# Remote.net
KiCad netlist of a schematic drawn in Altium Designer
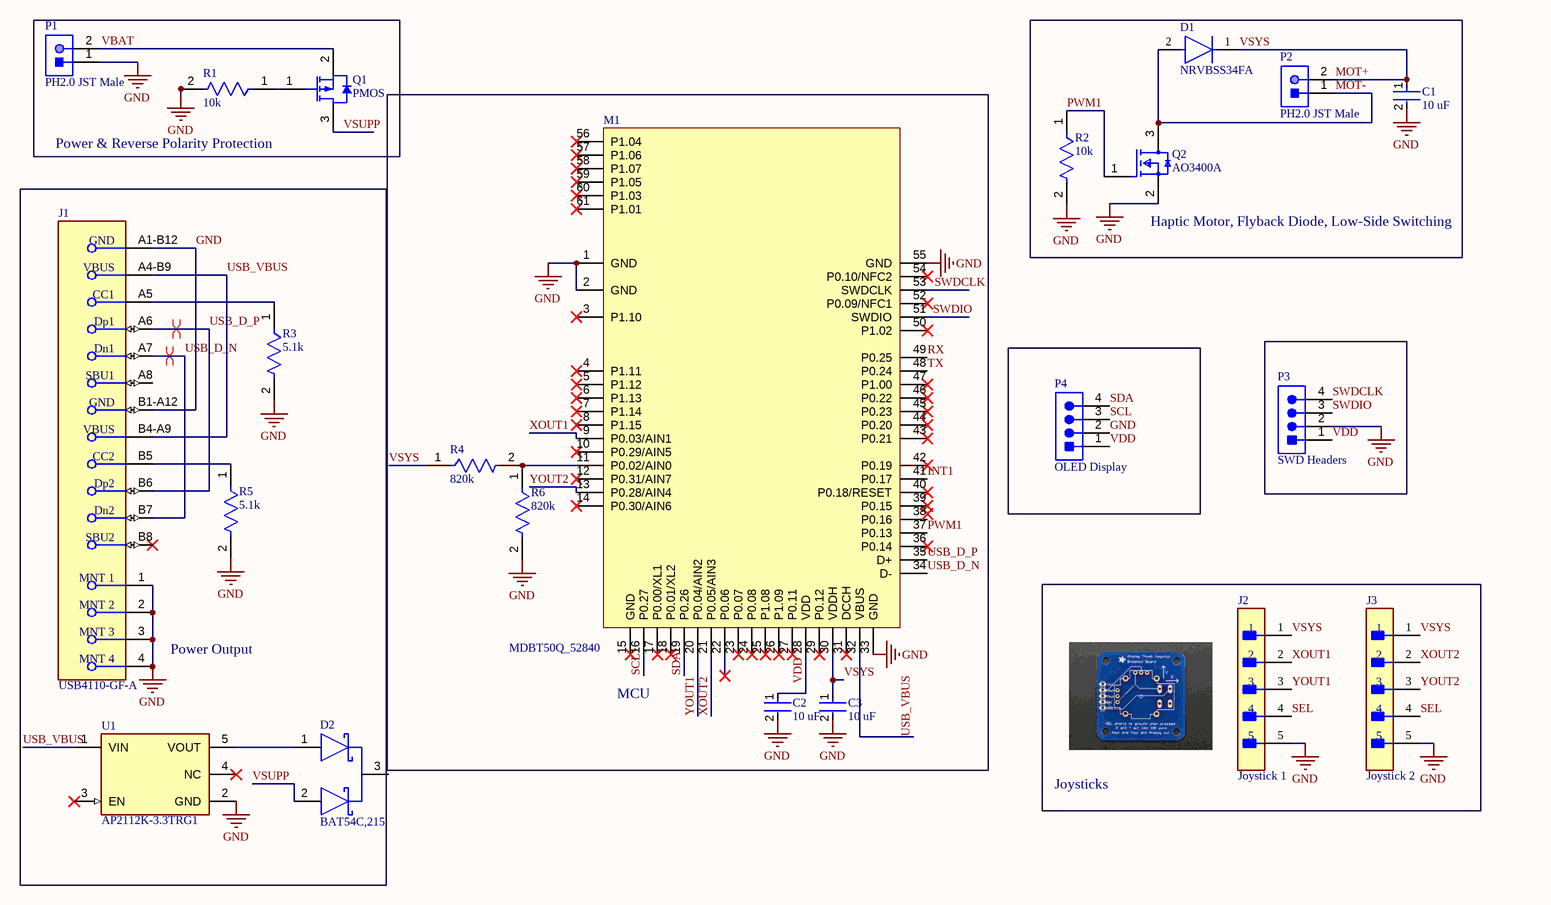
[diagram p0: Remote.SchDoc]

(export (version "E")
  (design (tool "Eeschema 10.0.6"))
  (components
    (comp (ref "C1")
      (value "10 uF")
      (footprint "FP-1210-L_3_3_0_4-W_2_5_0-IPC_A")
      (description "CAP CER 10UF 10V X7R 1210, 1210ZC106KAT2A")
      (fields (field (name "VOLTAGE") "10V") (field (name "TOLERANCE") "10%"))
      (libsource (lib "Altium Content Vault") (part "b4654b650e69147ec39a6b967a45e02"))
    )
    (comp (ref "C2")
      (value "10 uF")
      (footprint "FP-1210-L_3_3_0_4-W_2_5_0-IPC_A")
      (description "CAP CER 10UF 10V X7R 1210, 1210ZC106KAT2A")
      (fields (field (name "VOLTAGE") "10V") (field (name "TOLERANCE") "10%"))
      (libsource (lib "Altium Content Vault") (part "b4654b650e69147ec39a6b967a45e02"))
    )
    (comp (ref "C3")
      (value "10 uF")
      (footprint "FP-1210-L_3_3_0_4-W_2_5_0-IPC_A")
      (description "CAP CER 10UF 10V X7R 1210, 1210ZC106KAT2A")
      (fields (field (name "VOLTAGE") "10V") (field (name "TOLERANCE") "10%"))
      (libsource (lib "Altium Content Vault") (part "b4654b650e69147ec39a6b967a45e02"))
    )
    (comp (ref "D1")
      (value "NRVBSS34FA")
      (footprint "FP-425AB-MFG")
      (description "NRVBSS34FA Schottky Barrier Rectifier Diode 40V 3A 2-Pin SOD−123FL T/R")
      (libsource (lib "Altium Content Vault") (part "d7152d700b627762746794eb795d46e"))
    )
    (comp (ref "D2")
      (value "BAT54C,215")
      (footprint "FP-SOT23-MFG")
      (description "DIODE ARRAY SCHOTTKY 30V SOT23")
      (fields
        (field (name "MANUFACTURER") "Nexperia")
        (field (name "OCTOPART") "https://octopart.com/bat54c%2C215-nexperia-78738945")
      )
      (libsource (lib "Altium Content Vault") (part "933c91619b22c421400e34e7415f7b4"))
    )
    (comp (ref "J1")
      (value "USB4110-GF-A")
      (footprint "FP-USB4110-GF-A-MFG")
      (description "CONN USB 2.0 TYPE-C R/A SMT")
      (fields
        (field (name "OCTOPART") "https://octopart.com/usb4110-gf-a-gct-103941985")
        (field (name "MANUFACTURER") "GCT")
      )
      (libsource (lib "Altium Content Vault") (part "e23f2b38bb3c3f98e683ebab9ede730"))
    )
    (comp (ref "J2")
      (value "Joystick 1")
      (footprint "FP-22-28-4050-MFG")
      (libsource (lib "Altium Content Vault") (part "bf93c07fd2649a848d0ec8585582aab"))
    )
    (comp (ref "J3")
      (value "Joystick 2")
      (footprint "FP-22-28-4050-MFG")
      (libsource (lib "Altium Content Vault") (part "bf93c07fd2649a848d0ec8585582aab"))
    )
    (comp (ref "M1")
      (value "MDBT50Q_52840")
      (footprint "MDBT50Q")
      (description "MDBT50Q(52840)")
      (libsource (lib "MDBT50Q_52840_230606") (part "MDBT50Q_52840"))
    )
    (comp (ref "P1")
      (value "PH2.0 JST Male")
      (footprint "JST-S2B-PH-K-S_V")
      (fields (field (name "MANUFACTURER") "Japan Solderless Terminals"))
      (libsource (lib "Altium 365 Cloud") (part "CN-1P-M-R2"))
    )
    (comp (ref "P2")
      (value "PH2.0 JST Male")
      (footprint "JST-S2B-PH-K-S_V")
      (fields (field (name "MANUFACTURER") "Japan Solderless Terminals"))
      (libsource (lib "Altium 365 Cloud") (part "CN-1P-M-R2"))
    )
    (comp (ref "P3")
      (value "SWD Headers")
      (footprint "SLIN-GRPB041VWVN-RC_V")
      (fields (field (name "MANUFACTURER") "Sullins"))
      (libsource (lib "Altium Content Vault") (part "CN-1P-M-R4"))
    )
    (comp (ref "P4")
      (value "OLED Display")
      (footprint "SLIN-GRPB041VWVN-RC_V")
      (fields (field (name "MANUFACTURER") "Sullins"))
      (libsource (lib "Altium Content Vault") (part "CN-1P-M-R4"))
    )
    (comp (ref "Q1")
      (value "PMOS")
      (footprint "AO-SOT-23-3L_V")
      (description "P-Channel MOSFET, 30 V, 4 A, -55 to 150 degC, 3-Pin SOT-23-3L, RoHS, Tape and Reel, AO3401A")
      (fields (field (name "MANUFACTURER") "Alpha and Omega"))
      (libsource (lib "Altium Content Vault") (part "PEMOS-GSD-3"))
    )
    (comp (ref "Q2")
      (value "AO3400A")
      (footprint "FP-SOT23-MFG")
      (description "MOSFET N-CH 30V 5.7A SOT23")
      (libsource (lib "Altium Content Vault") (part "0a9ea7c96deaaede766a5b531c28de0"))
    )
    (comp (ref "R1")
      (value "10k")
      (footprint "FP-CRGCQ1210-IPC_C")
      (description "CRGCQ1210 10KΩ 0.5W ±100ppm/°C 5% 200V")
      (fields (field (name "TOLERANCE") "0.05") (field (name "MANUFACTURER PART NUMBER") "CRGCQ1210J10K"))
      (libsource (lib "Altium Content Vault") (part "1029c3af85768c4190bb7ad29bc67b5"))
    )
    (comp (ref "R2")
      (value "10k")
      (footprint "FP-CRGCQ1210-IPC_C")
      (description "CRGCQ1210 10KΩ 0.5W ±100ppm/°C 5% 200V")
      (fields (field (name "TOLERANCE") "0.05") (field (name "MANUFACTURER PART NUMBER") "CRGCQ1210J10K"))
      (libsource (lib "Altium Content Vault") (part "1029c3af85768c4190bb7ad29bc67b5"))
    )
    (comp (ref "R3")
      (value "5.1k")
      (footprint "FP-ESR10-IPC_C")
      (description "5.1kΩ ±5% 0.4W 0805 Anti-Surge Chip Resistor AEC-Q200")
      (fields (field (name "TOLERANCE") "5%"))
      (libsource (lib "Altium Content Vault") (part "1029c3af85768c4190bb7ad29bc67b5"))
    )
    (comp (ref "R4")
      (value "820k")
      (footprint "FP-AC1206-MFG")
      (description "RES SMD 820K OHM 1% 1/4W 1206, AC1206FR-07820KL")
      (fields
        (field (name "TOLERANCE") "0.01")
        (field (name "OCTOPART") "https://octopart.com/ac1206fr-07820kl-yageo-71368214")
      )
      (libsource (lib "Altium Content Vault") (part "1029c3af85768c4190bb7ad29bc67b5"))
    )
    (comp (ref "R5")
      (value "5.1k")
      (footprint "FP-ESR10-IPC_C")
      (description "5.1kΩ ±5% 0.4W 0805 Anti-Surge Chip Resistor AEC-Q200")
      (fields (field (name "TOLERANCE") "5%"))
      (libsource (lib "Altium Content Vault") (part "1029c3af85768c4190bb7ad29bc67b5"))
    )
    (comp (ref "R6")
      (value "820k")
      (footprint "FP-AC1206-MFG")
      (description "RES SMD 820K OHM 1% 1/4W 1206, AC1206FR-07820KL")
      (fields
        (field (name "TOLERANCE") "0.01")
        (field (name "OCTOPART") "https://octopart.com/ac1206fr-07820kl-yageo-71368214")
      )
      (libsource (lib "Altium Content Vault") (part "1029c3af85768c4190bb7ad29bc67b5"))
    )
    (comp (ref "U1")
      (value "AP2112K-3.3TRG1")
      (footprint "FP-SOT25-IPC_A")
      (description "IC REG LINEAR 3.3V 600MA SOT25")
      (libsource (lib "Altium Content Vault") (part "c8ab751aee5229183125ab046a11caa"))
    )
  )
  (nets
    (net (code "1") (name "/INT1") (class "Default")
      (node (ref "M1") (pin "41") (pinfunction "P0.17_41") (pintype "passive"))
    )
    (net (code "2") (name "/MOT+") (class "Default")
      (node (ref "C1") (pin "1") (pinfunction "1_1") (pintype "passive"))
      (node (ref "C3") (pin "1") (pinfunction "1_1") (pintype "passive"))
      (node (ref "D1") (pin "1") (pinfunction "C_1") (pintype "passive"))
      (node (ref "J2") (pin "1") (pinfunction "1_1") (pintype "passive"))
      (node (ref "J3") (pin "1") (pinfunction "1_1") (pintype "passive"))
      (node (ref "M1") (pin "30") (pinfunction "VDDH_30") (pintype "passive"))
      (node (ref "P2") (pin "2") (pinfunction "2_2") (pintype "passive"))
      (node (ref "R4") (pin "1") (pinfunction "1_1") (pintype "passive"))
    )
    (net (code "3") (name "/MOT-") (class "Default")
      (node (ref "D1") (pin "2") (pinfunction "A_2") (pintype "passive"))
      (node (ref "P2") (pin "1") (pinfunction "1_1") (pintype "passive"))
      (node (ref "Q2") (pin "3") (pinfunction "D_3") (pintype "passive"))
    )
    (net (code "4") (name "/PWM1") (class "Default")
      (node (ref "M1") (pin "37") (pinfunction "P0.13_37") (pintype "passive"))
      (node (ref "Q2") (pin "1") (pinfunction "G_1") (pintype "passive"))
      (node (ref "R2") (pin "1") (pinfunction "1_1") (pintype "passive"))
    )
    (net (code "5") (name "/RX") (class "Default")
      (node (ref "M1") (pin "49") (pinfunction "P0.25_49") (pintype "passive"))
    )
    (net (code "6") (name "/SCL") (class "Default")
      (node (ref "M1") (pin "16") (pinfunction "P0.27_16") (pintype "passive"))
      (node (ref "P4") (pin "3") (pinfunction "3_3") (pintype "passive"))
    )
    (net (code "7") (name "/SDA") (class "Default")
      (node (ref "M1") (pin "19") (pinfunction "P0.26_19") (pintype "passive"))
      (node (ref "P4") (pin "4") (pinfunction "4_4") (pintype "passive"))
    )
    (net (code "8") (name "/SEL") (class "Default")
      (node (ref "J2") (pin "4") (pinfunction "4_4") (pintype "passive"))
      (node (ref "J3") (pin "4") (pinfunction "4_4") (pintype "passive"))
    )
    (net (code "9") (name "/SWDCLK") (class "Default")
      (node (ref "M1") (pin "53") (pinfunction "SWDCLK_53") (pintype "passive"))
      (node (ref "P3") (pin "4") (pinfunction "4_4") (pintype "passive"))
    )
    (net (code "10") (name "/SWDIO") (class "Default")
      (node (ref "M1") (pin "51") (pinfunction "SWDIO_51") (pintype "passive"))
      (node (ref "P3") (pin "3") (pinfunction "3_3") (pintype "passive"))
    )
    (net (code "11") (name "/TX") (class "Default")
      (node (ref "M1") (pin "48") (pinfunction "P0.24_48") (pintype "passive"))
    )
    (net (code "12") (name "/USB_D_N") (class "Default")
      (node (ref "J1") (pin "A7") (pinfunction "Dn1_A7") (pintype "bidirectional"))
      (node (ref "J1") (pin "B7") (pinfunction "Dn2_B7") (pintype "bidirectional"))
      (node (ref "M1") (pin "34") (pinfunction "D-_34") (pintype "passive"))
    )
    (net (code "13") (name "/USB_D_P") (class "Default")
      (node (ref "J1") (pin "A6") (pinfunction "Dp1_A6") (pintype "bidirectional"))
      (node (ref "J1") (pin "B6") (pinfunction "Dp2_B6") (pintype "bidirectional"))
      (node (ref "M1") (pin "35") (pinfunction "D+_35") (pintype "passive"))
    )
    (net (code "14") (name "/USB_VBUS") (class "Default")
      (node (ref "J1") (pin "A4-B9") (pinfunction "VBUS_A4-B9") (pintype "power_in"))
      (node (ref "J1") (pin "B4-A9") (pinfunction "VBUS_B4-A9") (pintype "power_in"))
      (node (ref "M1") (pin "32") (pinfunction "VBUS_32") (pintype "passive"))
      (node (ref "U1") (pin "1") (pinfunction "VIN_1") (pintype "power_in"))
    )
    (net (code "15") (name "/VBAT") (class "Default")
      (node (ref "P1") (pin "2") (pinfunction "2_2") (pintype "passive"))
      (node (ref "Q1") (pin "2") (pinfunction "SOURCE_2") (pintype "passive"))
    )
    (net (code "16") (name "/VDD") (class "Default")
      (node (ref "C2") (pin "1") (pinfunction "1_1") (pintype "passive"))
      (node (ref "M1") (pin "28") (pinfunction "VDD_28") (pintype "passive"))
      (node (ref "P3") (pin "1") (pinfunction "1_1") (pintype "passive"))
      (node (ref "P4") (pin "1") (pinfunction "1_1") (pintype "passive"))
    )
    (net (code "17") (name "/VSUPP") (class "Default")
      (node (ref "D2") (pin "2") (pinfunction "2_ANODE_2") (pintype "passive"))
      (node (ref "Q1") (pin "3") (pinfunction "DRAIN_3") (pintype "passive"))
    )
    (net (code "18") (name "/XOUT1") (class "Default")
      (node (ref "J2") (pin "2") (pinfunction "2_2") (pintype "passive"))
      (node (ref "M1") (pin "9") (pinfunction "P0.03/AIN1_9") (pintype "passive"))
    )
    (net (code "19") (name "/XOUT2") (class "Default")
      (node (ref "J3") (pin "2") (pinfunction "2_2") (pintype "passive"))
      (node (ref "M1") (pin "21") (pinfunction "P0.05/AIN3_21") (pintype "passive"))
    )
    (net (code "20") (name "/YOUT1") (class "Default")
      (node (ref "J2") (pin "3") (pinfunction "3_3") (pintype "passive"))
      (node (ref "M1") (pin "20") (pinfunction "P0.04/AIN2_20") (pintype "passive"))
    )
    (net (code "21") (name "/YOUT2") (class "Default")
      (node (ref "J3") (pin "3") (pinfunction "3_3") (pintype "passive"))
      (node (ref "M1") (pin "13") (pinfunction "P0.28/AIN4_13") (pintype "passive"))
    )
    (net (code "22") (name "GND") (class "Default")
      (node (ref "C1") (pin "2") (pinfunction "2_2") (pintype "passive"))
      (node (ref "C2") (pin "2") (pinfunction "2_2") (pintype "passive"))
      (node (ref "C3") (pin "2") (pinfunction "2_2") (pintype "passive"))
      (node (ref "J1") (pin "1") (pinfunction "MNT_1_1") (pintype "passive"))
      (node (ref "J1") (pin "2") (pinfunction "MNT_2_2") (pintype "passive"))
      (node (ref "J1") (pin "3") (pinfunction "MNT_3_3") (pintype "passive"))
      (node (ref "J1") (pin "4") (pinfunction "MNT_4_4") (pintype "passive"))
      (node (ref "J1") (pin "A1-B12") (pinfunction "GND_A1-B12") (pintype "passive"))
      (node (ref "J1") (pin "B1-A12") (pinfunction "GND_B1-A12") (pintype "bidirectional"))
      (node (ref "J2") (pin "5") (pinfunction "5_5") (pintype "passive"))
      (node (ref "J3") (pin "5") (pinfunction "5_5") (pintype "passive"))
      (node (ref "M1") (pin "1") (pinfunction "GND_1") (pintype "passive"))
      (node (ref "M1") (pin "2") (pinfunction "GND_2") (pintype "passive"))
      (node (ref "M1") (pin "33") (pinfunction "GND_33") (pintype "passive"))
      (node (ref "M1") (pin "55") (pinfunction "GND_55") (pintype "passive"))
      (node (ref "P1") (pin "1") (pinfunction "1_1") (pintype "passive"))
      (node (ref "P3") (pin "2") (pinfunction "2_2") (pintype "passive"))
      (node (ref "P4") (pin "2") (pinfunction "2_2") (pintype "passive"))
      (node (ref "Q2") (pin "2") (pinfunction "S_2") (pintype "passive"))
      (node (ref "R1") (pin "2") (pinfunction "2_2") (pintype "passive"))
      (node (ref "R2") (pin "2") (pinfunction "2_2") (pintype "passive"))
      (node (ref "R3") (pin "2") (pinfunction "2_2") (pintype "passive"))
      (node (ref "R5") (pin "2") (pinfunction "2_2") (pintype "passive"))
      (node (ref "R6") (pin "2") (pinfunction "2_2") (pintype "passive"))
      (node (ref "U1") (pin "2") (pinfunction "GND_2") (pintype "power_in"))
    )
    (net (code "23") (name "Net-(D2-1_ANODE)") (class "Default")
      (node (ref "D2") (pin "1") (pinfunction "1_ANODE_1") (pintype "passive"))
      (node (ref "U1") (pin "5") (pinfunction "VOUT_5") (pintype "power_in"))
    )
    (net (code "24") (name "Net-(J1-CC1)") (class "Default")
      (node (ref "J1") (pin "A5") (pinfunction "CC1_A5") (pintype "power_in"))
      (node (ref "R3") (pin "1") (pinfunction "1_1") (pintype "passive"))
    )
    (net (code "25") (name "Net-(J1-CC2)") (class "Default")
      (node (ref "J1") (pin "B5") (pinfunction "CC2_B5") (pintype "power_in"))
      (node (ref "R5") (pin "1") (pinfunction "1_1") (pintype "passive"))
    )
    (net (code "26") (name "Net-(M1-P0.02{slash}AIN0)") (class "Default")
      (node (ref "M1") (pin "11") (pinfunction "P0.02/AIN0_11") (pintype "passive"))
      (node (ref "R4") (pin "2") (pinfunction "2_2") (pintype "passive"))
      (node (ref "R6") (pin "1") (pinfunction "1_1") (pintype "passive"))
    )
    (net (code "27") (name "Net-(Q1-GATE)") (class "Default")
      (node (ref "Q1") (pin "1") (pinfunction "GATE_1") (pintype "passive"))
      (node (ref "R1") (pin "1") (pinfunction "1_1") (pintype "passive"))
    )
    (net (code "28") (name "unconnected-(D2-COMMON_CATHODE-Pad3)") (class "Default")
      (node (ref "D2") (pin "3") (pinfunction "COMMON_CATHODE_3") (pintype "passive"))
    )
    (net (code "29") (name "unconnected-(J1-SBU1-PadA8)") (class "Default")
      (node (ref "J1") (pin "A8") (pinfunction "SBU1_A8") (pintype "bidirectional"))
    )
    (net (code "30") (name "unconnected-(J1-SBU2-PadB8)") (class "Default")
      (node (ref "J1") (pin "B8") (pinfunction "SBU2_B8") (pintype "bidirectional+no_connect"))
    )
    (net (code "31") (name "unconnected-(M1-DCCH-Pad31)") (class "Default")
      (node (ref "M1") (pin "31") (pinfunction "DCCH_31") (pintype "passive+no_connect"))
    )
    (net (code "32") (name "unconnected-(M1-GND-Pad15)") (class "Default")
      (node (ref "M1") (pin "15") (pinfunction "GND_15") (pintype "passive+no_connect"))
    )
    (net (code "33") (name "unconnected-(M1-P0.00{slash}XL1-Pad17)") (class "Default")
      (node (ref "M1") (pin "17") (pinfunction "P0.00/XL1_17") (pintype "passive+no_connect"))
    )
    (net (code "34") (name "unconnected-(M1-P0.01{slash}XL2-Pad18)") (class "Default")
      (node (ref "M1") (pin "18") (pinfunction "P0.01/XL2_18") (pintype "passive+no_connect"))
    )
    (net (code "35") (name "unconnected-(M1-P0.06-Pad22)") (class "Default")
      (node (ref "M1") (pin "22") (pinfunction "P0.06_22") (pintype "passive+no_connect"))
    )
    (net (code "36") (name "unconnected-(M1-P0.07-Pad23)") (class "Default")
      (node (ref "M1") (pin "23") (pinfunction "P0.07_23") (pintype "passive+no_connect"))
    )
    (net (code "37") (name "unconnected-(M1-P0.08-Pad24)") (class "Default")
      (node (ref "M1") (pin "24") (pinfunction "P0.08_24") (pintype "passive+no_connect"))
    )
    (net (code "38") (name "unconnected-(M1-P0.09{slash}NFC1-Pad52)") (class "Default")
      (node (ref "M1") (pin "52") (pinfunction "P0.09/NFC1_52") (pintype "passive+no_connect"))
    )
    (net (code "39") (name "unconnected-(M1-P0.10{slash}NFC2-Pad54)") (class "Default")
      (node (ref "M1") (pin "54") (pinfunction "P0.10/NFC2_54") (pintype "passive+no_connect"))
    )
    (net (code "40") (name "unconnected-(M1-P0.11-Pad27)") (class "Default")
      (node (ref "M1") (pin "27") (pinfunction "P0.11_27") (pintype "passive+no_connect"))
    )
    (net (code "41") (name "unconnected-(M1-P0.12-Pad29)") (class "Default")
      (node (ref "M1") (pin "29") (pinfunction "P0.12_29") (pintype "passive+no_connect"))
    )
    (net (code "42") (name "unconnected-(M1-P0.14-Pad36)") (class "Default")
      (node (ref "M1") (pin "36") (pinfunction "P0.14_36") (pintype "passive+no_connect"))
    )
    (net (code "43") (name "unconnected-(M1-P0.15-Pad39)") (class "Default")
      (node (ref "M1") (pin "39") (pinfunction "P0.15_39") (pintype "passive+no_connect"))
    )
    (net (code "44") (name "unconnected-(M1-P0.16-Pad38)") (class "Default")
      (node (ref "M1") (pin "38") (pinfunction "P0.16_38") (pintype "passive"))
    )
    (net (code "45") (name "unconnected-(M1-P0.18{slash}RESET-Pad40)") (class "Default")
      (node (ref "M1") (pin "40") (pinfunction "P0.18/RESET_40") (pintype "passive+no_connect"))
    )
    (net (code "46") (name "unconnected-(M1-P0.19-Pad42)") (class "Default")
      (node (ref "M1") (pin "42") (pinfunction "P0.19_42") (pintype "passive+no_connect"))
    )
    (net (code "47") (name "unconnected-(M1-P0.20-Pad44)") (class "Default")
      (node (ref "M1") (pin "44") (pinfunction "P0.20_44") (pintype "passive+no_connect"))
    )
    (net (code "48") (name "unconnected-(M1-P0.21-Pad43)") (class "Default")
      (node (ref "M1") (pin "43") (pinfunction "P0.21_43") (pintype "passive+no_connect"))
    )
    (net (code "49") (name "unconnected-(M1-P0.22-Pad46)") (class "Default")
      (node (ref "M1") (pin "46") (pinfunction "P0.22_46") (pintype "passive+no_connect"))
    )
    (net (code "50") (name "unconnected-(M1-P0.23-Pad45)") (class "Default")
      (node (ref "M1") (pin "45") (pinfunction "P0.23_45") (pintype "passive+no_connect"))
    )
    (net (code "51") (name "unconnected-(M1-P0.29{slash}AIN5-Pad10)") (class "Default")
      (node (ref "M1") (pin "10") (pinfunction "P0.29/AIN5_10") (pintype "passive+no_connect"))
    )
    (net (code "52") (name "unconnected-(M1-P0.30{slash}AIN6-Pad14)") (class "Default")
      (node (ref "M1") (pin "14") (pinfunction "P0.30/AIN6_14") (pintype "passive+no_connect"))
    )
    (net (code "53") (name "unconnected-(M1-P0.31{slash}AIN7-Pad12)") (class "Default")
      (node (ref "M1") (pin "12") (pinfunction "P0.31/AIN7_12") (pintype "passive+no_connect"))
    )
    (net (code "54") (name "unconnected-(M1-P1.00-Pad47)") (class "Default")
      (node (ref "M1") (pin "47") (pinfunction "P1.00_47") (pintype "passive+no_connect"))
    )
    (net (code "55") (name "unconnected-(M1-P1.01-Pad61)") (class "Default")
      (node (ref "M1") (pin "61") (pinfunction "P1.01_61") (pintype "passive+no_connect"))
    )
    (net (code "56") (name "unconnected-(M1-P1.02-Pad50)") (class "Default")
      (node (ref "M1") (pin "50") (pinfunction "P1.02_50") (pintype "passive+no_connect"))
    )
    (net (code "57") (name "unconnected-(M1-P1.03-Pad60)") (class "Default")
      (node (ref "M1") (pin "60") (pinfunction "P1.03_60") (pintype "passive+no_connect"))
    )
    (net (code "58") (name "unconnected-(M1-P1.04-Pad56)") (class "Default")
      (node (ref "M1") (pin "56") (pinfunction "P1.04_56") (pintype "passive+no_connect"))
    )
    (net (code "59") (name "unconnected-(M1-P1.05-Pad59)") (class "Default")
      (node (ref "M1") (pin "59") (pinfunction "P1.05_59") (pintype "passive+no_connect"))
    )
    (net (code "60") (name "unconnected-(M1-P1.06-Pad57)") (class "Default")
      (node (ref "M1") (pin "57") (pinfunction "P1.06_57") (pintype "passive+no_connect"))
    )
    (net (code "61") (name "unconnected-(M1-P1.07-Pad58)") (class "Default")
      (node (ref "M1") (pin "58") (pinfunction "P1.07_58") (pintype "passive+no_connect"))
    )
    (net (code "62") (name "unconnected-(M1-P1.08-Pad25)") (class "Default")
      (node (ref "M1") (pin "25") (pinfunction "P1.08_25") (pintype "passive+no_connect"))
    )
    (net (code "63") (name "unconnected-(M1-P1.09-Pad26)") (class "Default")
      (node (ref "M1") (pin "26") (pinfunction "P1.09_26") (pintype "passive+no_connect"))
    )
    (net (code "64") (name "unconnected-(M1-P1.10-Pad3)") (class "Default")
      (node (ref "M1") (pin "3") (pinfunction "P1.10_3") (pintype "passive+no_connect"))
    )
    (net (code "65") (name "unconnected-(M1-P1.11-Pad4)") (class "Default")
      (node (ref "M1") (pin "4") (pinfunction "P1.11_4") (pintype "passive+no_connect"))
    )
    (net (code "66") (name "unconnected-(M1-P1.12-Pad5)") (class "Default")
      (node (ref "M1") (pin "5") (pinfunction "P1.12_5") (pintype "passive+no_connect"))
    )
    (net (code "67") (name "unconnected-(M1-P1.13-Pad6)") (class "Default")
      (node (ref "M1") (pin "6") (pinfunction "P1.13_6") (pintype "passive+no_connect"))
    )
    (net (code "68") (name "unconnected-(M1-P1.14-Pad7)") (class "Default")
      (node (ref "M1") (pin "7") (pinfunction "P1.14_7") (pintype "passive+no_connect"))
    )
    (net (code "69") (name "unconnected-(M1-P1.15-Pad8)") (class "Default")
      (node (ref "M1") (pin "8") (pinfunction "P1.15_8") (pintype "passive+no_connect"))
    )
    (net (code "70") (name "unconnected-(U1-EN-Pad3)") (class "Default")
      (node (ref "U1") (pin "3") (pinfunction "EN_3") (pintype "input+no_connect"))
    )
    (net (code "71") (name "unconnected-(U1-NC-Pad4)") (class "Default")
      (node (ref "U1") (pin "4") (pinfunction "NC_4") (pintype "passive+no_connect"))
    )
  )
)
